# ESD_DWNSTRM.net
KiCad netlist of a schematic drawn in Altium Designer
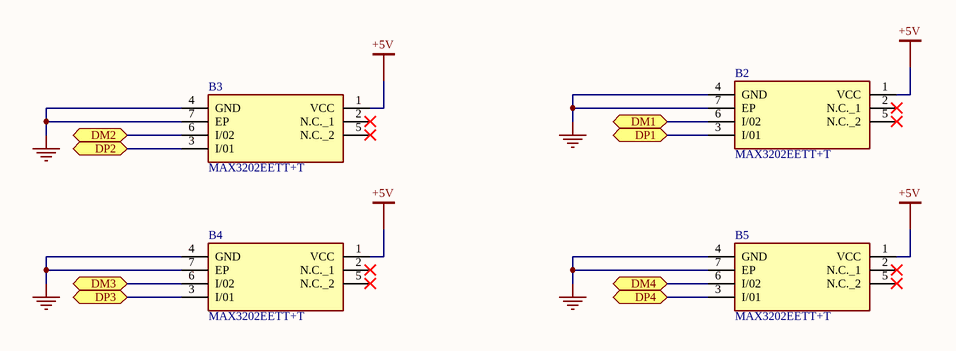
[diagram p0: ESD_DWNSTRM.SchDoc]

(export (version "E")
  (design (tool "Eeschema 10.0.6"))
  (components
    (comp (ref "B2")
      (value "MAX3202EETT+T")
      (footprint "SON95P300X300X80-7N")
      (fields (field (name "MOUSER PART NUMBER") "700-MAX3202EETTT"))
      (libsource (lib "Schematic-Lib-PhilsLab") (part "MAX3202EETT+T"))
    )
    (comp (ref "B3")
      (value "MAX3202EETT+T")
      (footprint "SON95P300X300X80-7N")
      (fields (field (name "MOUSER PART NUMBER") "700-MAX3202EETTT"))
      (libsource (lib "Schematic-Lib-PhilsLab") (part "MAX3202EETT+T"))
    )
    (comp (ref "B4")
      (value "MAX3202EETT+T")
      (footprint "SON95P300X300X80-7N")
      (fields (field (name "MOUSER PART NUMBER") "700-MAX3202EETTT"))
      (libsource (lib "Schematic-Lib-PhilsLab") (part "MAX3202EETT+T"))
    )
    (comp (ref "B5")
      (value "MAX3202EETT+T")
      (footprint "SON95P300X300X80-7N")
      (fields (field (name "MOUSER PART NUMBER") "700-MAX3202EETTT"))
      (libsource (lib "Schematic-Lib-PhilsLab") (part "MAX3202EETT+T"))
    )
  )
  (nets
    (net (code "1") (name "+5V") (class "Default")
      (node (ref "B2") (pin "1") (pinfunction "VCC_1") (pintype "passive"))
      (node (ref "B3") (pin "1") (pinfunction "VCC_1") (pintype "passive"))
      (node (ref "B4") (pin "1") (pinfunction "VCC_1") (pintype "passive"))
      (node (ref "B5") (pin "1") (pinfunction "VCC_1") (pintype "passive"))
    )
    (net (code "2") (name "/DM1") (class "Default")
      (node (ref "B2") (pin "6") (pinfunction "I/02_6") (pintype "passive"))
    )
    (net (code "3") (name "/DM2") (class "Default")
      (node (ref "B3") (pin "6") (pinfunction "I/02_6") (pintype "passive"))
    )
    (net (code "4") (name "/DM3") (class "Default")
      (node (ref "B4") (pin "6") (pinfunction "I/02_6") (pintype "passive"))
    )
    (net (code "5") (name "/DM4") (class "Default")
      (node (ref "B5") (pin "6") (pinfunction "I/02_6") (pintype "passive"))
    )
    (net (code "6") (name "/DP1") (class "Default")
      (node (ref "B2") (pin "3") (pinfunction "I/01_3") (pintype "passive"))
    )
    (net (code "7") (name "/DP2") (class "Default")
      (node (ref "B3") (pin "3") (pinfunction "I/01_3") (pintype "passive"))
    )
    (net (code "8") (name "/DP3") (class "Default")
      (node (ref "B4") (pin "3") (pinfunction "I/01_3") (pintype "passive"))
    )
    (net (code "9") (name "/DP4") (class "Default")
      (node (ref "B5") (pin "3") (pinfunction "I/01_3") (pintype "passive"))
    )
    (net (code "10") (name "GND") (class "Default")
      (node (ref "B2") (pin "4") (pinfunction "GND_4") (pintype "passive"))
      (node (ref "B2") (pin "7") (pinfunction "EP_7") (pintype "passive"))
      (node (ref "B3") (pin "4") (pinfunction "GND_4") (pintype "passive"))
      (node (ref "B3") (pin "7") (pinfunction "EP_7") (pintype "passive"))
      (node (ref "B4") (pin "4") (pinfunction "GND_4") (pintype "passive"))
      (node (ref "B4") (pin "7") (pinfunction "EP_7") (pintype "passive"))
      (node (ref "B5") (pin "4") (pinfunction "GND_4") (pintype "passive"))
      (node (ref "B5") (pin "7") (pinfunction "EP_7") (pintype "passive"))
    )
    (net (code "11") (name "unconnected-(B2-N.C._1-Pad2)") (class "Default")
      (node (ref "B2") (pin "2") (pinfunction "N.C._1_2") (pintype "passive+no_connect"))
    )
    (net (code "12") (name "unconnected-(B2-N.C._2-Pad5)") (class "Default")
      (node (ref "B2") (pin "5") (pinfunction "N.C._2_5") (pintype "passive+no_connect"))
    )
    (net (code "13") (name "unconnected-(B3-N.C._1-Pad2)") (class "Default")
      (node (ref "B3") (pin "2") (pinfunction "N.C._1_2") (pintype "passive+no_connect"))
    )
    (net (code "14") (name "unconnected-(B3-N.C._2-Pad5)") (class "Default")
      (node (ref "B3") (pin "5") (pinfunction "N.C._2_5") (pintype "passive+no_connect"))
    )
    (net (code "15") (name "unconnected-(B4-N.C._1-Pad2)") (class "Default")
      (node (ref "B4") (pin "2") (pinfunction "N.C._1_2") (pintype "passive+no_connect"))
    )
    (net (code "16") (name "unconnected-(B4-N.C._2-Pad5)") (class "Default")
      (node (ref "B4") (pin "5") (pinfunction "N.C._2_5") (pintype "passive+no_connect"))
    )
    (net (code "17") (name "unconnected-(B5-N.C._1-Pad2)") (class "Default")
      (node (ref "B5") (pin "2") (pinfunction "N.C._1_2") (pintype "passive+no_connect"))
    )
    (net (code "18") (name "unconnected-(B5-N.C._2-Pad5)") (class "Default")
      (node (ref "B5") (pin "5") (pinfunction "N.C._2_5") (pintype "passive+no_connect"))
    )
  )
)
